# leo_shield.net
KiCad netlist of a schematic drawn in EAGLE
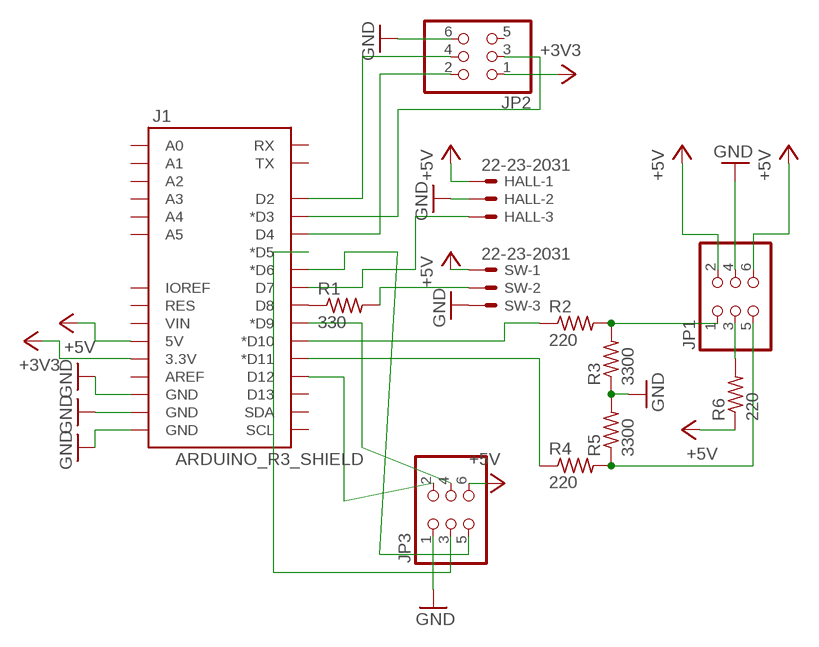
[diagram p0: schematic, sheet 1]

(export (version "E")
  (design (tool "Eeschema 10.0.6"))
  (components
    (comp (ref "HALL")
      (value "22-23-2031")
      (footprint "eagle-import:22-23-2031")
      (fields (field (name "MF") "MOLEX"))
      (libsource (lib "eagle-import") (part "22-23-2031"))
    )
    (comp (ref "J1")
      (value "ARDUINO_R3_SHIELD")
      (footprint "eagle-import:UNO_R3_SHIELD")
      (libsource (lib "eagle-import") (part "ARDUINO_R3_SHIELD"))
    )
    (comp (ref "JP1")
      (value "PINHD-2X3")
      (footprint "eagle-import:2X03")
      (libsource (lib "eagle-import") (part "PINHD-2X3"))
    )
    (comp (ref "JP2")
      (value "PINHD-2X3")
      (footprint "eagle-import:2X03")
      (libsource (lib "eagle-import") (part "PINHD-2X3"))
    )
    (comp (ref "JP3")
      (value "PINHD-2X3")
      (footprint "eagle-import:2X03")
      (libsource (lib "eagle-import") (part "PINHD-2X3"))
    )
    (comp (ref "R1")
      (value "330")
      (footprint "eagle-import:0204_7")
      (libsource (lib "eagle-import") (part "R-US_0204/7"))
    )
    (comp (ref "R2")
      (value "220")
      (footprint "eagle-import:0204_7")
      (libsource (lib "eagle-import") (part "R-US_0204/7"))
    )
    (comp (ref "R3")
      (value "3300")
      (footprint "eagle-import:0204_7")
      (libsource (lib "eagle-import") (part "R-US_0204/7"))
    )
    (comp (ref "R4")
      (value "220")
      (footprint "eagle-import:0204_7")
      (libsource (lib "eagle-import") (part "R-US_0204/7"))
    )
    (comp (ref "R5")
      (value "3300")
      (footprint "eagle-import:0204_7")
      (libsource (lib "eagle-import") (part "R-US_0204/7"))
    )
    (comp (ref "R6")
      (value "220")
      (footprint "eagle-import:0204_7")
      (libsource (lib "eagle-import") (part "R-US_0204/7"))
    )
    (comp (ref "SW")
      (value "22-23-2031")
      (footprint "eagle-import:22-23-2031")
      (fields (field (name "MF") "MOLEX"))
      (libsource (lib "eagle-import") (part "22-23-2031"))
    )
  )
  (nets
    (net (code "1") (name "+3V3") (class "Default")
      (node (ref "J1") (pin "3.3V") (pinfunction "3.3V_3.3V") (pintype "bidirectional"))
      (node (ref "JP2") (pin "1") (pinfunction "1_1") (pintype "passive"))
    )
    (net (code "2") (name "+5V") (class "Default")
      (node (ref "HALL") (pin "1") (pinfunction "S_1") (pintype "passive"))
      (node (ref "J1") (pin "5V") (pinfunction "5V_5V") (pintype "bidirectional"))
      (node (ref "JP1") (pin "2") (pinfunction "2_2") (pintype "passive"))
      (node (ref "JP1") (pin "6") (pinfunction "6_6") (pintype "passive"))
      (node (ref "JP3") (pin "6") (pinfunction "6_6") (pintype "passive"))
      (node (ref "R6") (pin "1") (pinfunction "1_1") (pintype "passive"))
      (node (ref "SW") (pin "1") (pinfunction "S_1") (pintype "passive"))
    )
    (net (code "3") (name "GND") (class "Default")
      (node (ref "HALL") (pin "2") (pinfunction "S_2") (pintype "passive"))
      (node (ref "J1") (pin "GND@0") (pinfunction "GND_GND@0") (pintype "bidirectional"))
      (node (ref "J1") (pin "GND@1") (pinfunction "GND_GND@1") (pintype "bidirectional"))
      (node (ref "J1") (pin "GND@2") (pinfunction "GND_GND@2") (pintype "bidirectional"))
      (node (ref "JP1") (pin "4") (pinfunction "4_4") (pintype "passive"))
      (node (ref "JP2") (pin "6") (pinfunction "6_6") (pintype "passive"))
      (node (ref "JP3") (pin "1") (pinfunction "1_1") (pintype "passive"))
      (node (ref "R3") (pin "1") (pinfunction "1_1") (pintype "passive"))
      (node (ref "R5") (pin "2") (pinfunction "2_2") (pintype "passive"))
      (node (ref "SW") (pin "3") (pinfunction "S_3") (pintype "passive"))
    )
    (net (code "4") (name "Net-(HALLC-S)") (class "Default")
      (node (ref "HALL") (pin "3") (pinfunction "S_3") (pintype "passive"))
      (node (ref "J1") (pin "D7") (pinfunction "D7_D7") (pintype "bidirectional"))
    )
    (net (code "5") (name "Net-(J1-*D3)") (class "Default")
      (node (ref "J1") (pin "D3") (pinfunction "*D3_D3") (pintype "bidirectional"))
      (node (ref "JP2") (pin "3") (pinfunction "3_3") (pintype "passive"))
    )
    (net (code "6") (name "Net-(J1-*D5)") (class "Default")
      (node (ref "J1") (pin "D5") (pinfunction "*D5_D5") (pintype "bidirectional"))
      (node (ref "JP3") (pin "3") (pinfunction "3_3") (pintype "passive"))
    )
    (net (code "7") (name "Net-(J1-*D6)") (class "Default")
      (node (ref "J1") (pin "D6") (pinfunction "*D6_D6") (pintype "bidirectional"))
      (node (ref "JP3") (pin "5") (pinfunction "5_5") (pintype "passive"))
    )
    (net (code "8") (name "Net-(J1-*D9)") (class "Default")
      (node (ref "J1") (pin "D9") (pinfunction "*D9_D9") (pintype "bidirectional"))
      (node (ref "JP3") (pin "4") (pinfunction "4_4") (pintype "passive"))
    )
    (net (code "9") (name "Net-(J1-*D10)") (class "Default")
      (node (ref "J1") (pin "D10") (pinfunction "*D10_D10") (pintype "bidirectional"))
      (node (ref "R2") (pin "1") (pinfunction "1_1") (pintype "passive"))
    )
    (net (code "10") (name "Net-(J1-*D11)") (class "Default")
      (node (ref "J1") (pin "D11") (pinfunction "*D11_D11") (pintype "bidirectional"))
      (node (ref "R4") (pin "1") (pinfunction "1_1") (pintype "passive"))
    )
    (net (code "11") (name "Net-(J1-PadD2)") (class "Default")
      (node (ref "J1") (pin "D2") (pinfunction "D2_D2") (pintype "bidirectional"))
      (node (ref "JP2") (pin "4") (pinfunction "4_4") (pintype "passive"))
    )
    (net (code "12") (name "Net-(J1-PadD4)") (class "Default")
      (node (ref "J1") (pin "D4") (pinfunction "D4_D4") (pintype "bidirectional"))
      (node (ref "JP2") (pin "2") (pinfunction "2_2") (pintype "passive"))
    )
    (net (code "13") (name "Net-(J1-PadD8)") (class "Default")
      (node (ref "J1") (pin "D8") (pinfunction "D8_D8") (pintype "bidirectional"))
      (node (ref "R1") (pin "1") (pinfunction "1_1") (pintype "passive"))
    )
    (net (code "14") (name "Net-(J1-PadD12)") (class "Default")
      (node (ref "J1") (pin "D12") (pinfunction "D12_D12") (pintype "bidirectional"))
      (node (ref "JP3") (pin "2") (pinfunction "2_2") (pintype "passive"))
    )
    (net (code "15") (name "Net-(JP1-Pad1)") (class "Default")
      (node (ref "JP1") (pin "1") (pinfunction "1_1") (pintype "passive"))
      (node (ref "R2") (pin "2") (pinfunction "2_2") (pintype "passive"))
      (node (ref "R3") (pin "2") (pinfunction "2_2") (pintype "passive"))
    )
    (net (code "16") (name "Net-(JP1-Pad3)") (class "Default")
      (node (ref "JP1") (pin "3") (pinfunction "3_3") (pintype "passive"))
      (node (ref "R6") (pin "2") (pinfunction "2_2") (pintype "passive"))
    )
    (net (code "17") (name "Net-(JP1-Pad5)") (class "Default")
      (node (ref "JP1") (pin "5") (pinfunction "5_5") (pintype "passive"))
      (node (ref "R4") (pin "2") (pinfunction "2_2") (pintype "passive"))
      (node (ref "R5") (pin "1") (pinfunction "1_1") (pintype "passive"))
    )
    (net (code "18") (name "Net-(SWB-S)") (class "Default")
      (node (ref "R1") (pin "2") (pinfunction "2_2") (pintype "passive"))
      (node (ref "SW") (pin "2") (pinfunction "S_2") (pintype "passive"))
    )
    (net (code "19") (name "unconnected-(J1-PadA0)") (class "Default")
      (node (ref "J1") (pin "A0") (pinfunction "A0_A0") (pintype "bidirectional"))
    )
    (net (code "20") (name "unconnected-(J1-PadA1)") (class "Default")
      (node (ref "J1") (pin "A1") (pinfunction "A1_A1") (pintype "bidirectional"))
    )
    (net (code "21") (name "unconnected-(J1-PadA2)") (class "Default")
      (node (ref "J1") (pin "A2") (pinfunction "A2_A2") (pintype "bidirectional"))
    )
    (net (code "22") (name "unconnected-(J1-PadA3)") (class "Default")
      (node (ref "J1") (pin "A3") (pinfunction "A3_A3") (pintype "bidirectional"))
    )
    (net (code "23") (name "unconnected-(J1-PadA4)") (class "Default")
      (node (ref "J1") (pin "A4") (pinfunction "A4_A4") (pintype "bidirectional"))
    )
    (net (code "24") (name "unconnected-(J1-PadA5)") (class "Default")
      (node (ref "J1") (pin "A5") (pinfunction "A5_A5") (pintype "bidirectional"))
    )
    (net (code "25") (name "unconnected-(J1-PadAREF)") (class "Default")
      (node (ref "J1") (pin "AREF") (pinfunction "AREF_AREF") (pintype "bidirectional"))
    )
    (net (code "26") (name "unconnected-(J1-PadD13)") (class "Default")
      (node (ref "J1") (pin "D13") (pinfunction "D13_D13") (pintype "bidirectional"))
    )
    (net (code "27") (name "unconnected-(J1-PadIOREF)") (class "Default")
      (node (ref "J1") (pin "IOREF") (pinfunction "IOREF_IOREF") (pintype "bidirectional"))
    )
    (net (code "28") (name "unconnected-(J1-PadRES)") (class "Default")
      (node (ref "J1") (pin "RES") (pinfunction "RES_RES") (pintype "bidirectional"))
    )
    (net (code "29") (name "unconnected-(J1-PadRX)") (class "Default")
      (node (ref "J1") (pin "RX") (pinfunction "RX_RX") (pintype "bidirectional"))
    )
    (net (code "30") (name "unconnected-(J1-PadSCL)") (class "Default")
      (node (ref "J1") (pin "SCL") (pinfunction "SCL_SCL") (pintype "bidirectional"))
    )
    (net (code "31") (name "unconnected-(J1-PadSDA)") (class "Default")
      (node (ref "J1") (pin "SDA") (pinfunction "SDA_SDA") (pintype "bidirectional"))
    )
    (net (code "32") (name "unconnected-(J1-PadTX)") (class "Default")
      (node (ref "J1") (pin "TX") (pinfunction "TX_TX") (pintype "bidirectional"))
    )
    (net (code "33") (name "unconnected-(J1-PadVIN)") (class "Default")
      (node (ref "J1") (pin "VIN") (pinfunction "VIN_VIN") (pintype "bidirectional"))
    )
    (net (code "34") (name "unconnected-(JP2-Pad5)") (class "Default")
      (node (ref "JP2") (pin "5") (pinfunction "5_5") (pintype "passive"))
    )
  )
)
